# Quad_Nand.net
KiCad netlist of a schematic drawn in Altium Designer
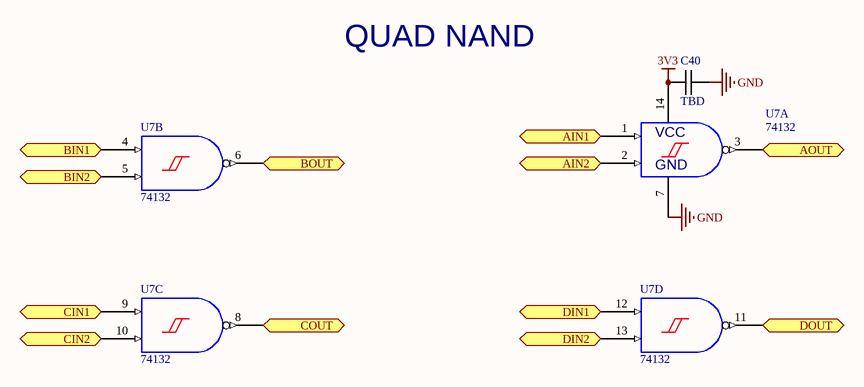
[diagram p0: Quad Nand.SchDoc]

(export (version "E")
  (design (tool "Eeschema 10.0.6"))
  (components
    (comp (ref "C40")
      (value "TBD")
      (footprint "1210C-GENERIC")
      (description "CAPACITOR 1210 CERAMIC VALUE TO BE DETERMINED")
      (libsource (lib "RVA_Altium_Library") (part "Passives_Capacitors_1210_1210C-TBD"))
    )
    (comp (ref "U7")
      (value "74132")
      (footprint "SSOP14")
      (description "QUAD 2-IN POS NAND SCH")
      (libsource (lib "RVA_Altium_Library") (part "74132"))
    )
  )
  (nets
    (net (code "1") (name "/AIN1") (class "Default") (node (ref "U7") (pin "1") (pintype "input")))
    (net (code "2") (name "/AIN2") (class "Default") (node (ref "U7") (pin "2") (pintype "input")))
    (net (code "3") (name "/AOUT") (class "Default") (node (ref "U7") (pin "3") (pintype "output")))
    (net (code "4") (name "/BIN1") (class "Default") (node (ref "U7") (pin "4") (pintype "input")))
    (net (code "5") (name "/BIN2") (class "Default") (node (ref "U7") (pin "5") (pintype "input")))
    (net (code "6") (name "/BOUT") (class "Default") (node (ref "U7") (pin "6") (pintype "output")))
    (net (code "7") (name "/CIN1") (class "Default") (node (ref "U7") (pin "9") (pintype "input")))
    (net (code "8") (name "/CIN2") (class "Default") (node (ref "U7") (pin "10") (pintype "input")))
    (net (code "9") (name "/COUT") (class "Default") (node (ref "U7") (pin "8") (pintype "output")))
    (net (code "10") (name "/DIN1") (class "Default") (node (ref "U7") (pin "12") (pintype "input")))
    (net (code "11") (name "/DIN2") (class "Default") (node (ref "U7") (pin "13") (pintype "input")))
    (net (code "12") (name "/DOUT") (class "Default") (node (ref "U7") (pin "11") (pintype "output")))
    (net (code "13") (name "3V3") (class "Default")
      (node (ref "C40") (pin "1") (pintype "passive"))
      (node (ref "U7") (pin "14") (pinfunction "VCC_14") (pintype "power_in"))
    )
    (net (code "14") (name "GND") (class "Default")
      (node (ref "C40") (pin "2") (pintype "passive"))
      (node (ref "U7") (pin "7") (pinfunction "GND_7") (pintype "power_in"))
    )
  )
)
